# 5VBoost.net
KiCad netlist of a schematic drawn in Altium Designer
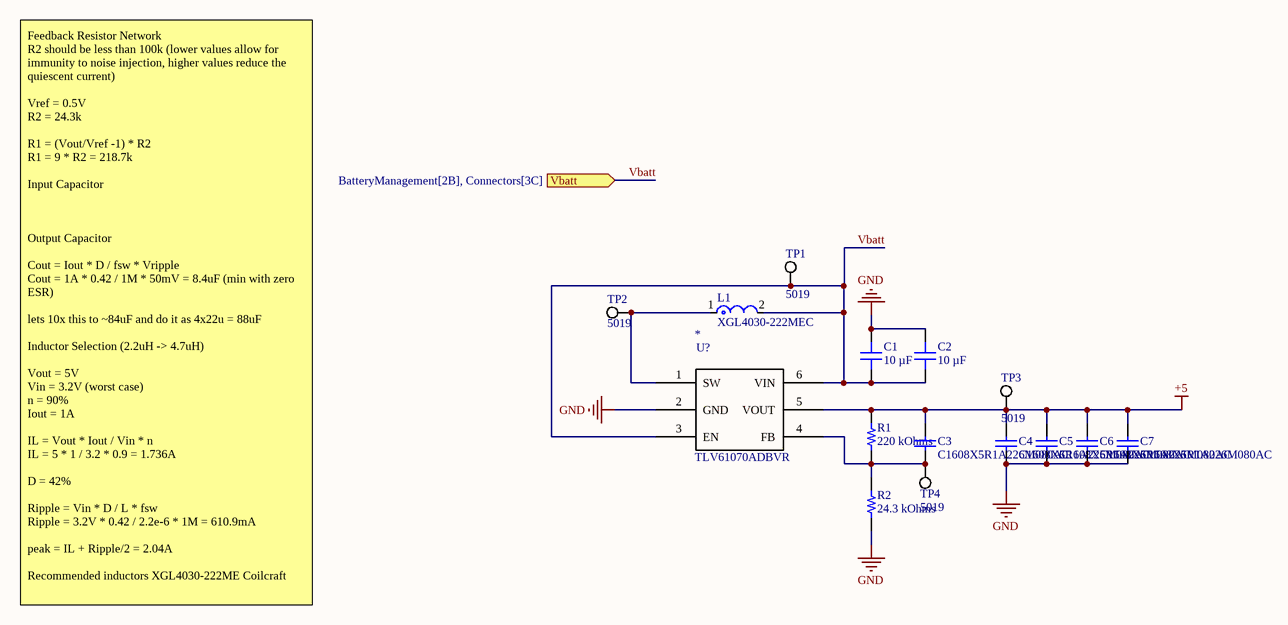
[diagram p0: 5VBoost.SchDoc]

(export (version "E")
  (design (tool "Eeschema 10.0.6"))
  (components
    (comp (ref "*")
      (value "TLV61070ADBVR")
      (footprint "SOT95P280X145-6N")
      (libsource (lib "2020-09-26_17-27-19") (part "TLV61070ADBVR"))
    )
    (comp (ref "C1")
      (value "10 µF")
      (footprint "CAP 0603_1608")
      (description "CAP CER 10UF 25V X5R 0603")
      (fields
        (field (name "PART NUMBER") "GRM188R61E106KA73J")
        (field (name "MANUFACTURER") "Murata Electronics")
      )
      (libsource (lib "Celestial Altium Library - altium_library") (part "Capacitor"))
    )
    (comp (ref "C2")
      (value "10 µF")
      (footprint "CAP 0603_1608")
      (description "CAP CER 10UF 25V X5R 0603")
      (fields
        (field (name "PART NUMBER") "GRM188R61E106KA73J")
        (field (name "MANUFACTURER") "Murata Electronics")
      )
      (libsource (lib "Celestial Altium Library - altium_library") (part "Capacitor"))
    )
    (comp (ref "C3")
      (value "C1608X5R1A226M080AC")
      (footprint "CAPC1608X100X20ML10")
      (description "Chip Capacitor, 22 uF, +/- 20%, 10 V, -55 to 85 degC, 0603 (1608 Metric), RoHS, Tape and Reel")
      (fields (field (name "MANUFACTURER") "TDK") (field (name "TOLERANCE") "±20%"))
      (libsource (lib "Altium Content Vault") (part "CAP-NP-2"))
    )
    (comp (ref "C4")
      (value "C1608X5R1A226M080AC")
      (footprint "CAPC1608X100X20ML10")
      (description "Chip Capacitor, 22 uF, +/- 20%, 10 V, -55 to 85 degC, 0603 (1608 Metric), RoHS, Tape and Reel")
      (fields (field (name "MANUFACTURER") "TDK") (field (name "TOLERANCE") "±20%"))
      (libsource (lib "Altium Content Vault") (part "CAP-NP-2"))
    )
    (comp (ref "C5")
      (value "C1608X5R1A226M080AC")
      (footprint "CAPC1608X100X20ML10")
      (description "Chip Capacitor, 22 uF, +/- 20%, 10 V, -55 to 85 degC, 0603 (1608 Metric), RoHS, Tape and Reel")
      (fields (field (name "MANUFACTURER") "TDK") (field (name "TOLERANCE") "±20%"))
      (libsource (lib "Altium Content Vault") (part "CAP-NP-2"))
    )
    (comp (ref "C6")
      (value "C1608X5R1A226M080AC")
      (footprint "CAPC1608X100X20ML10")
      (description "Chip Capacitor, 22 uF, +/- 20%, 10 V, -55 to 85 degC, 0603 (1608 Metric), RoHS, Tape and Reel")
      (fields (field (name "MANUFACTURER") "TDK") (field (name "TOLERANCE") "±20%"))
      (libsource (lib "Altium Content Vault") (part "CAP-NP-2"))
    )
    (comp (ref "C7")
      (value "C1608X5R1A226M080AC")
      (footprint "CAPC1608X100X20ML10")
      (description "Chip Capacitor, 22 uF, +/- 20%, 10 V, -55 to 85 degC, 0603 (1608 Metric), RoHS, Tape and Reel")
      (fields (field (name "MANUFACTURER") "TDK") (field (name "TOLERANCE") "±20%"))
      (libsource (lib "Altium Content Vault") (part "CAP-NP-2"))
    )
    (comp (ref "L1")
      (value "XGL4030-222MEC")
      (footprint "FP-XGL4030-MFG")
      (description "Inductor Power Shielded Wirewound 2.2uH 20% 1MHz Composite 8.7A 15mOhm DCR Automotive T/R")
      (libsource (lib "Altium Content Vault") (part "4cc4b267dca4c8e51f7102f422741d8"))
    )
    (comp (ref "R1")
      (value "220 kOhms")
      (footprint "RES 0603_1608")
      (description "RES 220K OHM 1% 1/10W 0603")
      (fields (field (name "PART NUMBER") "RC0603FR-07220KL") (field (name "MANUFACTURER") "Yageo"))
      (libsource (lib "Celestial Altium Library - altium_library") (part "Resistor"))
    )
    (comp (ref "R2")
      (value "24.3 kOhms")
      (footprint "RES 0603_1608")
      (description "RES 24.3K OHM 1% 1/10W 0603")
      (fields (field (name "PART NUMBER") "RC0603FR-0724K3L") (field (name "MANUFACTURER") "Yageo"))
      (libsource (lib "Celestial Altium Library - altium_library") (part "Resistor"))
    )
    (comp (ref "TP1")
      (value "5019")
      (footprint "KSTN-5019_V")
      (description "Test Point, 1 Position SMD, RoHS, Tape and Reel")
      (libsource (lib "Altium Content Vault") (part "TESTPOINT_WHITE"))
    )
    (comp (ref "TP2")
      (value "5019")
      (footprint "KSTN-5019_V")
      (description "Test Point, 1 Position SMD, RoHS, Tape and Reel")
      (libsource (lib "Altium Content Vault") (part "TESTPOINT_WHITE"))
    )
    (comp (ref "TP3")
      (value "5019")
      (footprint "KSTN-5019_V")
      (description "Test Point, 1 Position SMD, RoHS, Tape and Reel")
      (libsource (lib "Altium Content Vault") (part "TESTPOINT_WHITE"))
    )
    (comp (ref "TP4")
      (value "5019")
      (footprint "KSTN-5019_V")
      (description "Test Point, 1 Position SMD, RoHS, Tape and Reel")
      (libsource (lib "Altium Content Vault") (part "TESTPOINT_WHITE"))
    )
  )
  (nets
    (net (code "1") (name "+5") (class "Default")
      (node (ref "*") (pin "5") (pinfunction "VOUT_5") (pintype "passive"))
      (node (ref "C3") (pin "2") (pinfunction "2_2") (pintype "passive"))
      (node (ref "C4") (pin "2") (pinfunction "2_2") (pintype "passive"))
      (node (ref "C5") (pin "2") (pinfunction "2_2") (pintype "passive"))
      (node (ref "C6") (pin "2") (pinfunction "2_2") (pintype "passive"))
      (node (ref "C7") (pin "2") (pinfunction "2_2") (pintype "passive"))
      (node (ref "R1") (pin "2") (pinfunction "2_2") (pintype "passive"))
      (node (ref "TP3") (pin "1") (pinfunction "1_1") (pintype "passive"))
    )
    (net (code "2") (name "/Vbatt") (class "Default")
      (node (ref "*") (pin "3") (pinfunction "EN_3") (pintype "passive"))
      (node (ref "*") (pin "6") (pinfunction "VIN_6") (pintype "passive"))
      (node (ref "C1") (pin "1") (pinfunction "1_1") (pintype "passive"))
      (node (ref "C2") (pin "1") (pinfunction "1_1") (pintype "passive"))
      (node (ref "L1") (pin "2") (pinfunction "2_2") (pintype "passive"))
      (node (ref "TP1") (pin "1") (pinfunction "1_1") (pintype "passive"))
    )
    (net (code "3") (name "GND") (class "Default")
      (node (ref "*") (pin "2") (pinfunction "GND_2") (pintype "passive"))
      (node (ref "C1") (pin "2") (pinfunction "2_2") (pintype "passive"))
      (node (ref "C2") (pin "2") (pinfunction "2_2") (pintype "passive"))
      (node (ref "C4") (pin "1") (pinfunction "1_1") (pintype "passive"))
      (node (ref "C5") (pin "1") (pinfunction "1_1") (pintype "passive"))
      (node (ref "C6") (pin "1") (pinfunction "1_1") (pintype "passive"))
      (node (ref "C7") (pin "1") (pinfunction "1_1") (pintype "passive"))
      (node (ref "R2") (pin "1") (pinfunction "1_1") (pintype "passive"))
    )
    (net (code "4") (name "Net-(*-FB)") (class "Default")
      (node (ref "*") (pin "4") (pinfunction "FB_4") (pintype "passive"))
      (node (ref "C3") (pin "1") (pinfunction "1_1") (pintype "passive"))
      (node (ref "R1") (pin "1") (pinfunction "1_1") (pintype "passive"))
      (node (ref "R2") (pin "2") (pinfunction "2_2") (pintype "passive"))
      (node (ref "TP4") (pin "1") (pinfunction "1_1") (pintype "passive"))
    )
    (net (code "5") (name "Net-(*-SW)") (class "Default")
      (node (ref "*") (pin "1") (pinfunction "SW_1") (pintype "passive"))
      (node (ref "L1") (pin "1") (pinfunction "1_1") (pintype "passive"))
      (node (ref "TP2") (pin "1") (pinfunction "1_1") (pintype "passive"))
    )
  )
)
